# 74595.net
KiCad netlist of a schematic drawn in EAGLE
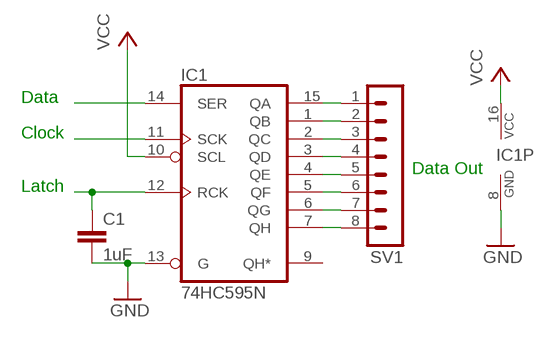
[diagram p0: schematic, sheet 1]

(export (version "E")
  (design (tool "Eeschema 10.0.6"))
  (components
    (comp (ref "C1")
      (value "1uF")
      (footprint "eagle-import:C025-024X044")
      (libsource (lib "eagle-import") (part "C-EU025-024X044"))
    )
    (comp (ref "IC1")
      (value "74HC595N")
      (footprint "eagle-import:DIL16")
      (libsource (lib "eagle-import") (part "74595NHC"))
    )
    (comp (ref "SV1")
      (value "MA08-1")
      (footprint "eagle-import:MA08-1")
      (libsource (lib "eagle-import") (part "MA08-1"))
    )
  )
  (nets
    (net (code "1") (name "GND") (class "Default")
      (node (ref "C1") (pin "2") (pinfunction "2_2") (pintype "passive"))
      (node (ref "IC1") (pin "13") (pinfunction "G_13") (pintype "input"))
      (node (ref "IC1") (pin "8") (pinfunction "GND_8") (pintype "power_in"))
    )
    (net (code "2") (name "Net-(IC1A-QA)") (class "Default")
      (node (ref "IC1") (pin "15") (pinfunction "QA_15") (pintype "tri_state"))
      (node (ref "SV1") (pin "1") (pinfunction "1_1") (pintype "passive"))
    )
    (net (code "3") (name "Net-(IC1A-QB)") (class "Default")
      (node (ref "IC1") (pin "1") (pinfunction "QB_1") (pintype "tri_state"))
      (node (ref "SV1") (pin "2") (pinfunction "2_2") (pintype "passive"))
    )
    (net (code "4") (name "Net-(IC1A-QC)") (class "Default")
      (node (ref "IC1") (pin "2") (pinfunction "QC_2") (pintype "tri_state"))
      (node (ref "SV1") (pin "3") (pinfunction "3_3") (pintype "passive"))
    )
    (net (code "5") (name "Net-(IC1A-QD)") (class "Default")
      (node (ref "IC1") (pin "3") (pinfunction "QD_3") (pintype "tri_state"))
      (node (ref "SV1") (pin "4") (pinfunction "4_4") (pintype "passive"))
    )
    (net (code "6") (name "Net-(IC1A-QE)") (class "Default")
      (node (ref "IC1") (pin "4") (pinfunction "QE_4") (pintype "tri_state"))
      (node (ref "SV1") (pin "5") (pinfunction "5_5") (pintype "passive"))
    )
    (net (code "7") (name "Net-(IC1A-QF)") (class "Default")
      (node (ref "IC1") (pin "5") (pinfunction "QF_5") (pintype "tri_state"))
      (node (ref "SV1") (pin "6") (pinfunction "6_6") (pintype "passive"))
    )
    (net (code "8") (name "Net-(IC1A-QG)") (class "Default")
      (node (ref "IC1") (pin "6") (pinfunction "QG_6") (pintype "tri_state"))
      (node (ref "SV1") (pin "7") (pinfunction "7_7") (pintype "passive"))
    )
    (net (code "9") (name "Net-(IC1A-QH)") (class "Default")
      (node (ref "IC1") (pin "7") (pinfunction "QH_7") (pintype "tri_state"))
      (node (ref "SV1") (pin "8") (pinfunction "8_8") (pintype "passive"))
    )
    (net (code "10") (name "Net-(IC1A-RCK)") (class "Default")
      (node (ref "C1") (pin "1") (pinfunction "1_1") (pintype "passive"))
      (node (ref "IC1") (pin "12") (pinfunction "RCK_12") (pintype "input"))
    )
    (net (code "11") (name "VCC") (class "Default")
      (node (ref "IC1") (pin "10") (pinfunction "SCL_10") (pintype "input"))
      (node (ref "IC1") (pin "16") (pinfunction "VCC_16") (pintype "power_in"))
    )
    (net (code "12") (name "unconnected-(IC1A-QH*-Pad9)") (class "Default")
      (node (ref "IC1") (pin "9") (pinfunction "QH*_9") (pintype "tri_state"))
    )
    (net (code "13") (name "unconnected-(IC1A-SCK-Pad11)") (class "Default")
      (node (ref "IC1") (pin "11") (pinfunction "SCK_11") (pintype "input"))
    )
    (net (code "14") (name "unconnected-(IC1A-SER-Pad14)") (class "Default")
      (node (ref "IC1") (pin "14") (pinfunction "SER_14") (pintype "input"))
    )
  )
)
